# Versa64Cart_v1_6.net
KiCad netlist of a schematic drawn in EAGLE
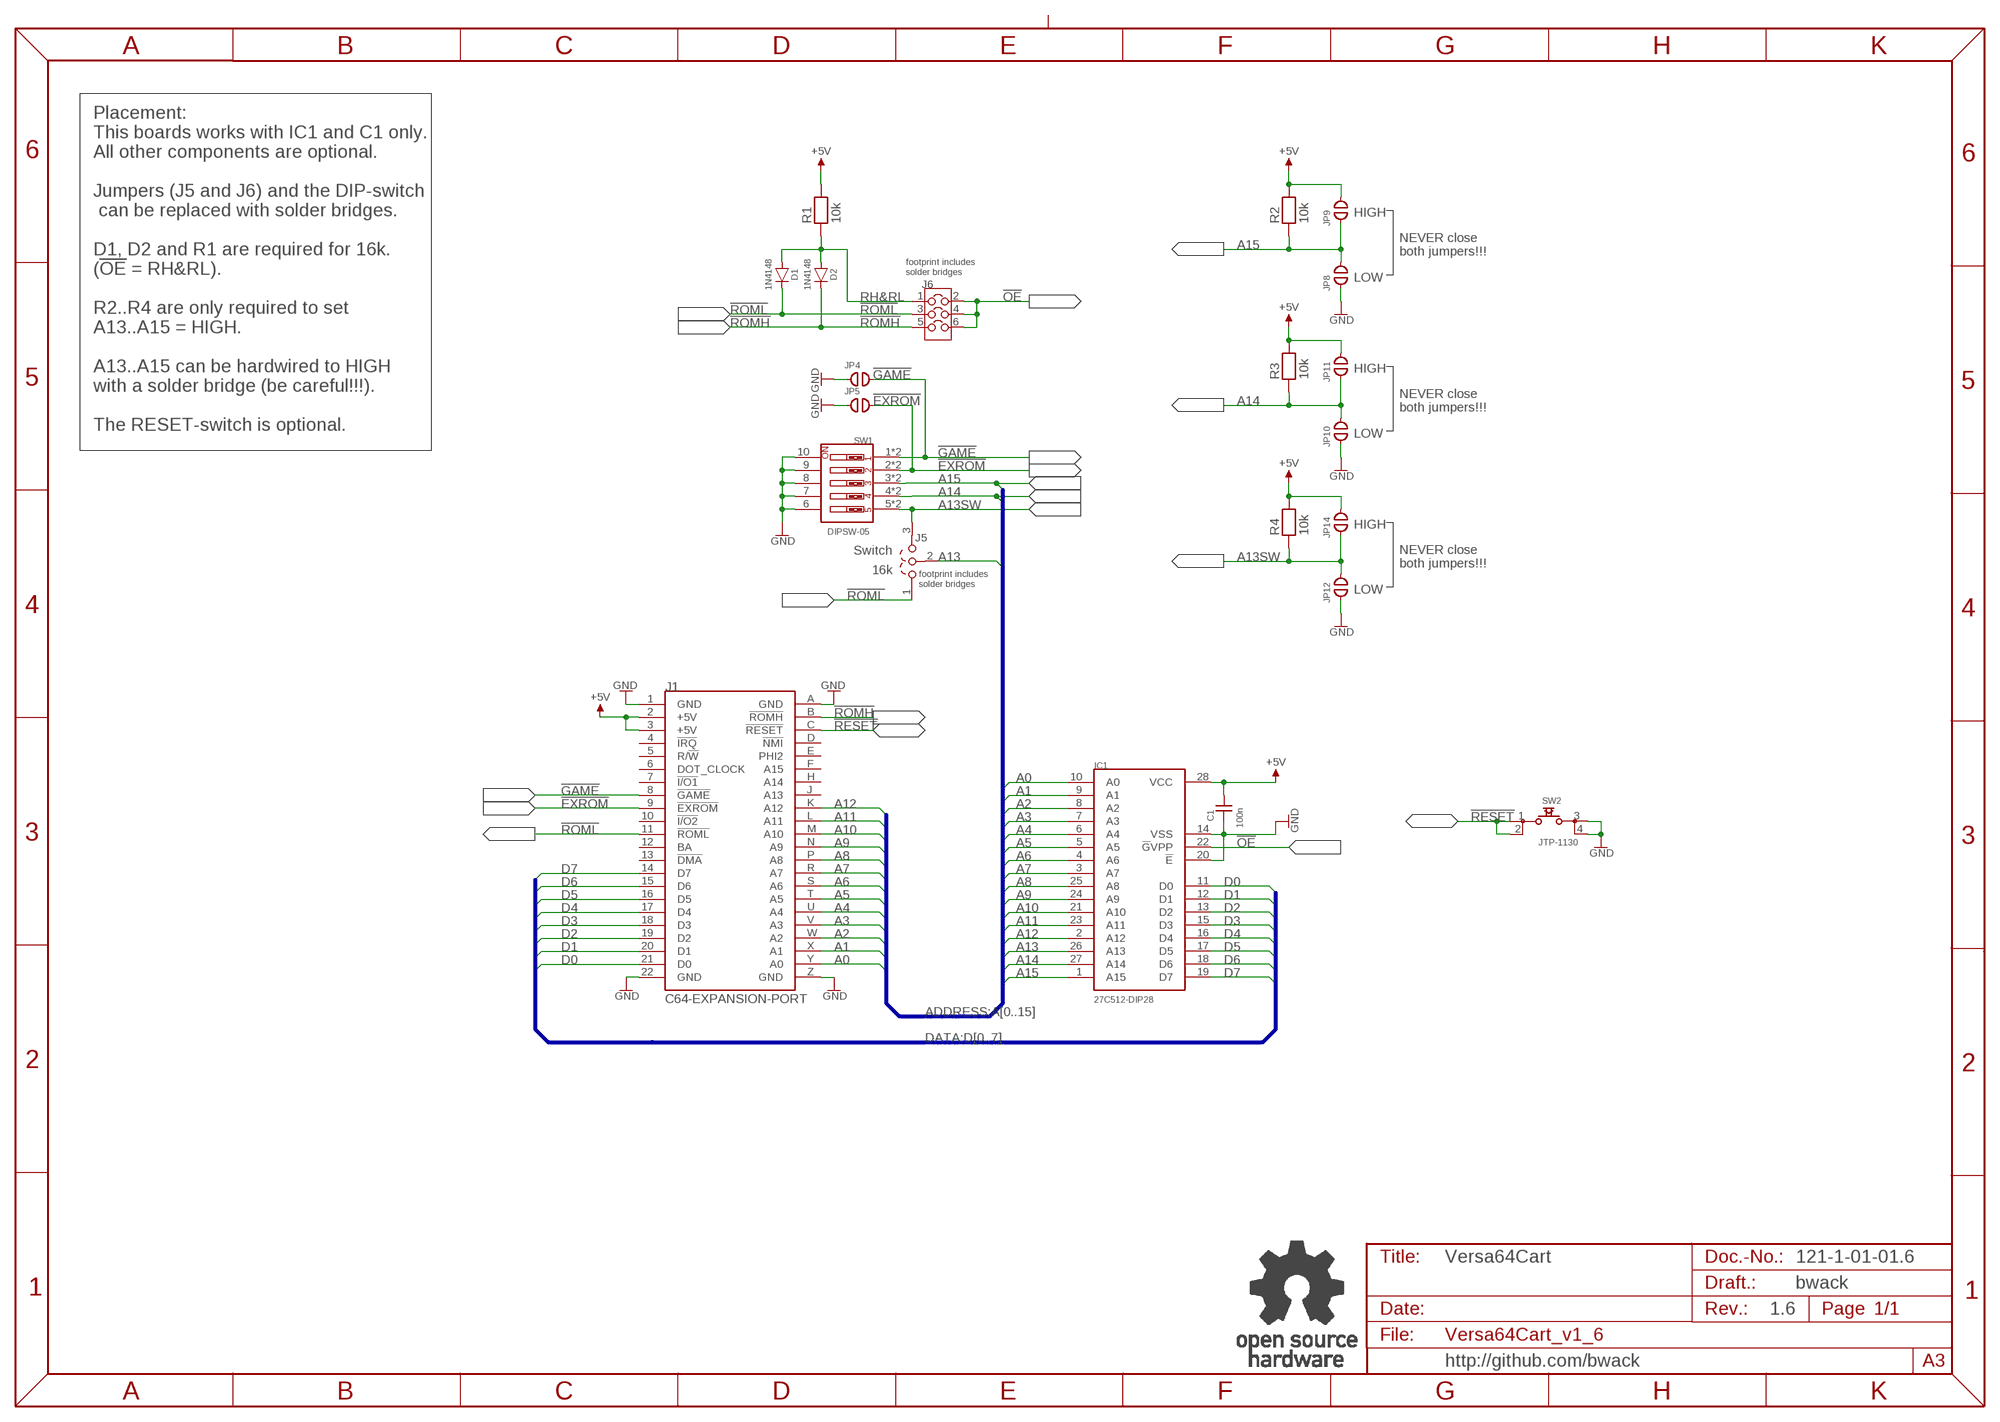
[diagram p0: schematic, sheet 1]

(export (version "E")
  (design (tool "Eeschema 10.0.6"))
  (components
    (comp (ref "C1")
      (value "100n")
      (footprint "eagle-import:C-2,5")
      (libsource (lib "eagle-import") (part "CAP01"))
    )
    (comp (ref "D1")
      (value "1N4148")
      (footprint "eagle-import:DO-35")
      (libsource (lib "eagle-import") (part "1N4148"))
    )
    (comp (ref "D2")
      (value "1N4148")
      (footprint "eagle-import:DO-35")
      (libsource (lib "eagle-import") (part "1N4148"))
    )
    (comp (ref "IC1")
      (value "27C512-DIP28")
      (footprint "eagle-import:DIL28-6")
      (libsource (lib "eagle-import") (part "M27C512-DIP28"))
    )
    (comp (ref "J1")
      (value "C64-EXPANSION-PORT")
      (footprint "eagle-import:EXPANSIO_SQ")
      (libsource (lib "eagle-import") (part "C64-EXPANSIONPNARROW"))
    )
    (comp (ref "J5")
      (value "COMBI-3P")
      (footprint "eagle-import:COMBI-3P")
      (libsource (lib "eagle-import") (part "COMBI-3P"))
    )
    (comp (ref "J6")
      (value "COMBI-3X2P")
      (footprint "eagle-import:COMBI-3X2")
      (fields (field (name "SPICEPREFIX") "X"))
      (libsource (lib "eagle-import") (part "COMBI-3X2P"))
    )
    (comp (ref "JP4")
      (value "OPEN")
      (footprint "eagle-import:CP_OP")
      (libsource (lib "eagle-import") (part "OPEN"))
    )
    (comp (ref "JP5")
      (value "OPEN")
      (footprint "eagle-import:CP_OP")
      (libsource (lib "eagle-import") (part "OPEN"))
    )
    (comp (ref "JP8")
      (value "OPEN")
      (footprint "eagle-import:CP_OP")
      (libsource (lib "eagle-import") (part "OPEN"))
    )
    (comp (ref "JP9")
      (value "OPEN")
      (footprint "eagle-import:CP_OP")
      (libsource (lib "eagle-import") (part "OPEN"))
    )
    (comp (ref "JP10")
      (value "OPEN")
      (footprint "eagle-import:CP_OP")
      (libsource (lib "eagle-import") (part "OPEN"))
    )
    (comp (ref "JP11")
      (value "OPEN")
      (footprint "eagle-import:CP_OP")
      (libsource (lib "eagle-import") (part "OPEN"))
    )
    (comp (ref "JP12")
      (value "OPEN")
      (footprint "eagle-import:CP_OP")
      (libsource (lib "eagle-import") (part "OPEN"))
    )
    (comp (ref "JP14")
      (value "OPEN")
      (footprint "eagle-import:CP_OP")
      (libsource (lib "eagle-import") (part "OPEN"))
    )
    (comp (ref "R1")
      (value "10k")
      (footprint "eagle-import:R-10")
      (libsource (lib "eagle-import") (part "RES04"))
    )
    (comp (ref "R2")
      (value "10k")
      (footprint "eagle-import:R-10")
      (libsource (lib "eagle-import") (part "RES04"))
    )
    (comp (ref "R3")
      (value "10k")
      (footprint "eagle-import:R-10")
      (libsource (lib "eagle-import") (part "RES04"))
    )
    (comp (ref "R4")
      (value "10k")
      (footprint "eagle-import:R-10")
      (libsource (lib "eagle-import") (part "RES04"))
    )
    (comp (ref "SW1")
      (value "DIPSW-05")
      (footprint "eagle-import:DIPSW-05VJ")
      (libsource (lib "eagle-import") (part "DIPSW-05"))
    )
    (comp (ref "SW2")
      (value "JTP-1130")
      (footprint "eagle-import:JTP-1130")
      (libsource (lib "eagle-import") (part "JTP-1130"))
    )
    (comp (ref "U$43")
      (value "OPEN_SOURCE_HW")
      (footprint "eagle-import:OPENHW")
      (libsource (lib "eagle-import") (part "OPEN_SOURCE_HW"))
    )
  )
  (nets
    (net (code "25") (name "+5V") (class "Default")
      (node (ref "C1") (pin "2") (pinfunction "2_2") (pintype "passive"))
      (node (ref "IC1") (pin "28") (pinfunction "VCC_28") (pintype "power_in"))
      (node (ref "J1") (pin "2") (pinfunction "+5V_2") (pintype "power_in"))
      (node (ref "J1") (pin "3") (pinfunction "+5V_3") (pintype "power_in"))
      (node (ref "JP11") (pin "2") (pinfunction "2_2") (pintype "passive"))
      (node (ref "JP14") (pin "2") (pinfunction "2_2") (pintype "passive"))
      (node (ref "JP9") (pin "2") (pinfunction "2_2") (pintype "passive"))
      (node (ref "R1") (pin "2") (pinfunction "2_2") (pintype "passive"))
      (node (ref "R2") (pin "2") (pinfunction "2_2") (pintype "passive"))
      (node (ref "R3") (pin "2") (pinfunction "2_2") (pintype "passive"))
      (node (ref "R4") (pin "2") (pinfunction "2_2") (pintype "passive"))
    )
    (net (code "26") (name "/A0") (class "Default")
      (node (ref "IC1") (pin "10") (pinfunction "A0_10") (pintype "input"))
      (node (ref "J1") (pin "Y") (pinfunction "A0_Y") (pintype "bidirectional"))
    )
    (net (code "27") (name "/A1") (class "Default")
      (node (ref "IC1") (pin "9") (pinfunction "A1_9") (pintype "input"))
      (node (ref "J1") (pin "X") (pinfunction "A1_X") (pintype "bidirectional"))
    )
    (net (code "28") (name "/A2") (class "Default")
      (node (ref "IC1") (pin "8") (pinfunction "A2_8") (pintype "input"))
      (node (ref "J1") (pin "W") (pinfunction "A2_W") (pintype "bidirectional"))
    )
    (net (code "29") (name "/A3") (class "Default")
      (node (ref "IC1") (pin "7") (pinfunction "A3_7") (pintype "input"))
      (node (ref "J1") (pin "V") (pinfunction "A3_V") (pintype "bidirectional"))
    )
    (net (code "30") (name "/A4") (class "Default")
      (node (ref "IC1") (pin "6") (pinfunction "A4_6") (pintype "input"))
      (node (ref "J1") (pin "U") (pinfunction "A4_U") (pintype "bidirectional"))
    )
    (net (code "31") (name "/A5") (class "Default")
      (node (ref "IC1") (pin "5") (pinfunction "A5_5") (pintype "input"))
      (node (ref "J1") (pin "T") (pinfunction "A5_T") (pintype "bidirectional"))
    )
    (net (code "32") (name "/A6") (class "Default")
      (node (ref "IC1") (pin "4") (pinfunction "A6_4") (pintype "input"))
      (node (ref "J1") (pin "S") (pinfunction "A6_S") (pintype "bidirectional"))
    )
    (net (code "33") (name "/A7") (class "Default")
      (node (ref "IC1") (pin "3") (pinfunction "A7_3") (pintype "input"))
      (node (ref "J1") (pin "R") (pinfunction "A7_R") (pintype "bidirectional"))
    )
    (net (code "34") (name "/A8") (class "Default")
      (node (ref "IC1") (pin "25") (pinfunction "A8_25") (pintype "input"))
      (node (ref "J1") (pin "P") (pinfunction "A8_P") (pintype "bidirectional"))
    )
    (net (code "35") (name "/A9") (class "Default")
      (node (ref "IC1") (pin "24") (pinfunction "A9_24") (pintype "input"))
      (node (ref "J1") (pin "N") (pinfunction "A9_N") (pintype "bidirectional"))
    )
    (net (code "36") (name "/A10") (class "Default")
      (node (ref "IC1") (pin "21") (pinfunction "A10_21") (pintype "input"))
      (node (ref "J1") (pin "M") (pinfunction "A10_M") (pintype "bidirectional"))
    )
    (net (code "37") (name "/A11") (class "Default")
      (node (ref "IC1") (pin "23") (pinfunction "A11_23") (pintype "input"))
      (node (ref "J1") (pin "L") (pinfunction "A11_L") (pintype "bidirectional"))
    )
    (net (code "38") (name "/A12") (class "Default")
      (node (ref "IC1") (pin "2") (pinfunction "A12_2") (pintype "input"))
      (node (ref "J1") (pin "K") (pinfunction "A12_K") (pintype "bidirectional"))
    )
    (net (code "39") (name "/A13") (class "Default")
      (node (ref "IC1") (pin "26") (pinfunction "A13_26") (pintype "input"))
      (node (ref "J5") (pin "2") (pinfunction "2_2") (pintype "bidirectional"))
    )
    (net (code "40") (name "/A13SW") (class "Default")
      (node (ref "J5") (pin "3") (pinfunction "3_3") (pintype "bidirectional"))
      (node (ref "JP12") (pin "2") (pinfunction "2_2") (pintype "passive"))
      (node (ref "JP14") (pin "1") (pinfunction "1_1") (pintype "passive"))
      (node (ref "R4") (pin "1") (pinfunction "1_1") (pintype "passive"))
      (node (ref "SW1") (pin "5") (pinfunction "5_5") (pintype "passive"))
      (node (ref "SW1") (pin "5J") (pinfunction "5_5J") (pintype "passive"))
    )
    (net (code "41") (name "/A14") (class "Default")
      (node (ref "IC1") (pin "27") (pinfunction "A14_27") (pintype "input"))
      (node (ref "JP10") (pin "2") (pinfunction "2_2") (pintype "passive"))
      (node (ref "JP11") (pin "1") (pinfunction "1_1") (pintype "passive"))
      (node (ref "R3") (pin "1") (pinfunction "1_1") (pintype "passive"))
      (node (ref "SW1") (pin "4") (pinfunction "4_4") (pintype "passive"))
      (node (ref "SW1") (pin "4J") (pinfunction "4_4J") (pintype "passive"))
    )
    (net (code "42") (name "/A15") (class "Default")
      (node (ref "IC1") (pin "1") (pinfunction "A15_1") (pintype "input"))
      (node (ref "JP8") (pin "2") (pinfunction "2_2") (pintype "passive"))
      (node (ref "JP9") (pin "1") (pinfunction "1_1") (pintype "passive"))
      (node (ref "R2") (pin "1") (pinfunction "1_1") (pintype "passive"))
      (node (ref "SW1") (pin "3") (pinfunction "3_3") (pintype "passive"))
      (node (ref "SW1") (pin "3J") (pinfunction "3_3J") (pintype "passive"))
    )
    (net (code "44") (name "/D0") (class "Default")
      (node (ref "IC1") (pin "11") (pinfunction "D0_11") (pintype "bidirectional"))
      (node (ref "J1") (pin "21") (pinfunction "D0_21") (pintype "bidirectional"))
    )
    (net (code "45") (name "/D1") (class "Default")
      (node (ref "IC1") (pin "12") (pinfunction "D1_12") (pintype "bidirectional"))
      (node (ref "J1") (pin "20") (pinfunction "D1_20") (pintype "bidirectional"))
    )
    (net (code "46") (name "/D2") (class "Default")
      (node (ref "IC1") (pin "13") (pinfunction "D2_13") (pintype "bidirectional"))
      (node (ref "J1") (pin "19") (pinfunction "D2_19") (pintype "bidirectional"))
    )
    (net (code "47") (name "/D3") (class "Default")
      (node (ref "IC1") (pin "15") (pinfunction "D3_15") (pintype "bidirectional"))
      (node (ref "J1") (pin "18") (pinfunction "D3_18") (pintype "bidirectional"))
    )
    (net (code "48") (name "/D4") (class "Default")
      (node (ref "IC1") (pin "16") (pinfunction "D4_16") (pintype "bidirectional"))
      (node (ref "J1") (pin "17") (pinfunction "D4_17") (pintype "bidirectional"))
    )
    (net (code "49") (name "/D5") (class "Default")
      (node (ref "IC1") (pin "17") (pinfunction "D5_17") (pintype "bidirectional"))
      (node (ref "J1") (pin "16") (pinfunction "D5_16") (pintype "bidirectional"))
    )
    (net (code "50") (name "/D6") (class "Default")
      (node (ref "IC1") (pin "18") (pinfunction "D6_18") (pintype "bidirectional"))
      (node (ref "J1") (pin "15") (pinfunction "D6_15") (pintype "bidirectional"))
    )
    (net (code "51") (name "/D7") (class "Default")
      (node (ref "IC1") (pin "19") (pinfunction "D7_19") (pintype "bidirectional"))
      (node (ref "J1") (pin "14") (pinfunction "D7_14") (pintype "bidirectional"))
    )
    (net (code "53") (name "/RH&RL") (class "Default")
      (node (ref "D1") (pin "A") (pinfunction "A_A") (pintype "passive"))
      (node (ref "D2") (pin "A") (pinfunction "A_A") (pintype "passive"))
      (node (ref "J6") (pin "1") (pinfunction "1_1") (pintype "bidirectional"))
      (node (ref "R1") (pin "1") (pinfunction "1_1") (pintype "passive"))
    )
    (net (code "54") (name "/~{EXROM}") (class "Default")
      (node (ref "J1") (pin "9") (pinfunction "~{EXROM}_9") (pintype "input"))
      (node (ref "JP5") (pin "2") (pinfunction "2_2") (pintype "passive"))
      (node (ref "SW1") (pin "2") (pinfunction "2_2") (pintype "passive"))
      (node (ref "SW1") (pin "2J") (pinfunction "2_2J") (pintype "passive"))
    )
    (net (code "55") (name "/~{GAME}") (class "Default")
      (node (ref "J1") (pin "8") (pinfunction "~{GAME}_8") (pintype "input"))
      (node (ref "JP4") (pin "2") (pinfunction "2_2") (pintype "passive"))
      (node (ref "SW1") (pin "1") (pinfunction "1_1") (pintype "passive"))
      (node (ref "SW1") (pin "1J") (pinfunction "1_1J") (pintype "passive"))
    )
    (net (code "56") (name "/~{OE}") (class "Default")
      (node (ref "IC1") (pin "22") (pinfunction "~{G}VPP_22") (pintype "input"))
      (node (ref "J6") (pin "2") (pinfunction "2_2") (pintype "bidirectional"))
      (node (ref "J6") (pin "4") (pinfunction "4_4") (pintype "bidirectional"))
      (node (ref "J6") (pin "6") (pinfunction "6_6") (pintype "bidirectional"))
    )
    (net (code "57") (name "/~{RESET}") (class "Default")
      (node (ref "J1") (pin "C") (pinfunction "~{RESET}_C") (pintype "open_collector"))
      (node (ref "SW2") (pin "1") (pinfunction "1_1") (pintype "passive"))
      (node (ref "SW2") (pin "2") (pinfunction "2_2") (pintype "passive"))
    )
    (net (code "58") (name "/~{ROMH}") (class "Default")
      (node (ref "D2") (pin "K") (pinfunction "K_K") (pintype "passive"))
      (node (ref "J1") (pin "B") (pinfunction "~{ROMH}_B") (pintype "output"))
      (node (ref "J6") (pin "5") (pinfunction "5_5") (pintype "bidirectional"))
    )
    (net (code "59") (name "/~{ROML}") (class "Default")
      (node (ref "D1") (pin "K") (pinfunction "K_K") (pintype "passive"))
      (node (ref "J1") (pin "11") (pinfunction "~{ROML}_11") (pintype "output"))
      (node (ref "J5") (pin "1") (pinfunction "1_1") (pintype "bidirectional"))
      (node (ref "J6") (pin "3") (pinfunction "3_3") (pintype "bidirectional"))
    )
    (net (code "60") (name "GND") (class "Default")
      (node (ref "C1") (pin "1") (pinfunction "1_1") (pintype "passive"))
      (node (ref "IC1") (pin "14") (pinfunction "VSS_14") (pintype "power_in"))
      (node (ref "IC1") (pin "20") (pinfunction "~{E}_20") (pintype "input"))
      (node (ref "J1") (pin "1") (pinfunction "GND_1") (pintype "power_in"))
      (node (ref "J1") (pin "22") (pinfunction "GND_22") (pintype "power_in"))
      (node (ref "J1") (pin "A") (pinfunction "GND_A") (pintype "power_in"))
      (node (ref "J1") (pin "Z") (pinfunction "GND_Z") (pintype "power_in"))
      (node (ref "JP10") (pin "1") (pinfunction "1_1") (pintype "passive"))
      (node (ref "JP12") (pin "1") (pinfunction "1_1") (pintype "passive"))
      (node (ref "JP4") (pin "1") (pinfunction "1_1") (pintype "passive"))
      (node (ref "JP5") (pin "1") (pinfunction "1_1") (pintype "passive"))
      (node (ref "JP8") (pin "1") (pinfunction "1_1") (pintype "passive"))
      (node (ref "SW1") (pin "10") (pinfunction "10_10") (pintype "passive"))
      (node (ref "SW1") (pin "6") (pinfunction "6_6") (pintype "passive"))
      (node (ref "SW1") (pin "7") (pinfunction "7_7") (pintype "passive"))
      (node (ref "SW1") (pin "8") (pinfunction "8_8") (pintype "passive"))
      (node (ref "SW1") (pin "9") (pinfunction "9_9") (pintype "passive"))
      (node (ref "SW2") (pin "3") (pinfunction "3_3") (pintype "passive"))
      (node (ref "SW2") (pin "4") (pinfunction "4_4") (pintype "passive"))
    )
    (net (code "61") (name "unconnected-(J1-A13-PadJ)") (class "Default")
      (node (ref "J1") (pin "J") (pinfunction "A13_J") (pintype "bidirectional"))
    )
    (net (code "62") (name "unconnected-(J1-A14-PadH)") (class "Default")
      (node (ref "J1") (pin "H") (pinfunction "A14_H") (pintype "bidirectional"))
    )
    (net (code "63") (name "unconnected-(J1-A15-PadF)") (class "Default")
      (node (ref "J1") (pin "F") (pinfunction "A15_F") (pintype "bidirectional"))
    )
    (net (code "64") (name "unconnected-(J1-BA-Pad12)") (class "Default")
      (node (ref "J1") (pin "12") (pinfunction "BA_12") (pintype "output"))
    )
    (net (code "65") (name "unconnected-(J1-DOT_CLOCK-Pad6)") (class "Default")
      (node (ref "J1") (pin "6") (pinfunction "DOT_CLOCK_6") (pintype "output"))
    )
    (net (code "66") (name "unconnected-(J1-PHI2-PadE)") (class "Default")
      (node (ref "J1") (pin "E") (pinfunction "PHI2_E") (pintype "output"))
    )
    (net (code "67") (name "unconnected-(J1-R{slash}~{W}-Pad5)") (class "Default")
      (node (ref "J1") (pin "5") (pinfunction "R/~{W}_5") (pintype "output"))
    )
    (net (code "68") (name "unconnected-(J1-~{DMA}-Pad13)") (class "Default")
      (node (ref "J1") (pin "13") (pinfunction "~{DMA}_13") (pintype "input"))
    )
    (net (code "69") (name "unconnected-(J1-~{IRQ}-Pad4)") (class "Default")
      (node (ref "J1") (pin "4") (pinfunction "~{IRQ}_4") (pintype "input"))
    )
    (net (code "70") (name "unconnected-(J1-~{I{slash}O1}-Pad7)") (class "Default")
      (node (ref "J1") (pin "7") (pinfunction "~{I/O1}_7") (pintype "output"))
    )
    (net (code "71") (name "unconnected-(J1-~{I{slash}O2}-Pad10)") (class "Default")
      (node (ref "J1") (pin "10") (pinfunction "~{I/O2}_10") (pintype "output"))
    )
    (net (code "72") (name "unconnected-(J1-~{NMI}-PadD)") (class "Default")
      (node (ref "J1") (pin "D") (pinfunction "~{NMI}_D") (pintype "input"))
    )
  )
)
